# trill-breakout.net
KiCad netlist of a schematic drawn in EAGLE
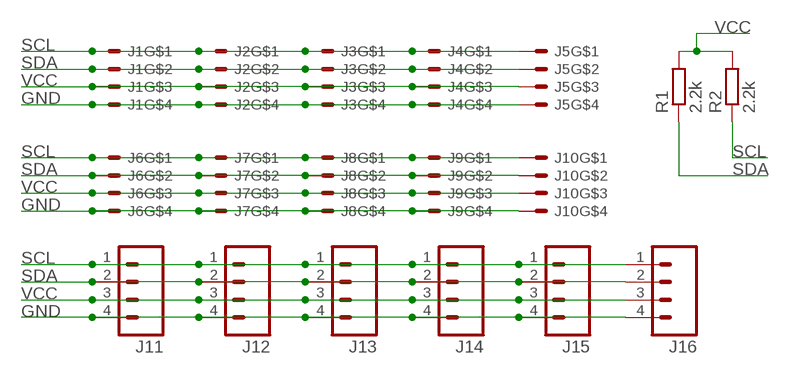
[diagram p0: schematic, sheet 1]

(export (version "E")
  (design (tool "Eeschema 10.0.6"))
  (components
    (comp (ref "J1")
      (value "GROVE-SMT")
      (footprint "eagle-import:JST-PH-4-SMT")
      (libsource (lib "eagle-import") (part "GROVE-SMT"))
    )
    (comp (ref "J2")
      (value "GROVE-SMT")
      (footprint "eagle-import:JST-PH-4-SMT")
      (libsource (lib "eagle-import") (part "GROVE-SMT"))
    )
    (comp (ref "J3")
      (value "GROVE-SMT")
      (footprint "eagle-import:JST-PH-4-SMT")
      (libsource (lib "eagle-import") (part "GROVE-SMT"))
    )
    (comp (ref "J4")
      (value "GROVE-SMT")
      (footprint "eagle-import:JST-PH-4-SMT")
      (libsource (lib "eagle-import") (part "GROVE-SMT"))
    )
    (comp (ref "J5")
      (value "GROVE-SMT")
      (footprint "eagle-import:JST-PH-4-SMT")
      (libsource (lib "eagle-import") (part "GROVE-SMT"))
    )
    (comp (ref "J6")
      (value "GROVE-SMT")
      (footprint "eagle-import:JST-PH-4-SMT")
      (libsource (lib "eagle-import") (part "GROVE-SMT"))
    )
    (comp (ref "J7")
      (value "GROVE-SMT")
      (footprint "eagle-import:JST-PH-4-SMT")
      (libsource (lib "eagle-import") (part "GROVE-SMT"))
    )
    (comp (ref "J8")
      (value "GROVE-SMT")
      (footprint "eagle-import:JST-PH-4-SMT")
      (libsource (lib "eagle-import") (part "GROVE-SMT"))
    )
    (comp (ref "J9")
      (value "GROVE-SMT")
      (footprint "eagle-import:JST-PH-4-SMT")
      (libsource (lib "eagle-import") (part "GROVE-SMT"))
    )
    (comp (ref "J10")
      (value "GROVE-SMT")
      (footprint "eagle-import:JST-PH-4-SMT")
      (libsource (lib "eagle-import") (part "GROVE-SMT"))
    )
    (comp (ref "J11")
      (value "M04LONGPADS")
      (footprint "eagle-import:1X04_LONGPADS")
      (libsource (lib "eagle-import") (part "M04LONGPADS"))
    )
    (comp (ref "J12")
      (value "M04LONGPADS")
      (footprint "eagle-import:1X04_LONGPADS")
      (libsource (lib "eagle-import") (part "M04LONGPADS"))
    )
    (comp (ref "J13")
      (value "M04LONGPADS")
      (footprint "eagle-import:1X04_LONGPADS")
      (libsource (lib "eagle-import") (part "M04LONGPADS"))
    )
    (comp (ref "J14")
      (value "M04LONGPADS")
      (footprint "eagle-import:1X04_LONGPADS")
      (libsource (lib "eagle-import") (part "M04LONGPADS"))
    )
    (comp (ref "J15")
      (value "M04LONGPADS")
      (footprint "eagle-import:1X04_LONGPADS")
      (libsource (lib "eagle-import") (part "M04LONGPADS"))
    )
    (comp (ref "J16")
      (value "M04LONGPADS")
      (footprint "eagle-import:1X04_LONGPADS")
      (libsource (lib "eagle-import") (part "M04LONGPADS"))
    )
    (comp (ref "R1")
      (value "2.2k")
      (footprint "eagle-import:R0603")
      (libsource (lib "eagle-import") (part "R-EU_R0603"))
    )
    (comp (ref "R2")
      (value "2.2k")
      (footprint "eagle-import:R0603")
      (libsource (lib "eagle-import") (part "R-EU_R0603"))
    )
  )
  (nets
    (net (code "1") (name "/GND") (class "Default")
      (node (ref "J1") (pin "4") (pinfunction "S_4") (pintype "passive"))
      (node (ref "J10") (pin "4") (pinfunction "S_4") (pintype "passive"))
      (node (ref "J11") (pin "4") (pinfunction "4_4") (pintype "passive"))
      (node (ref "J12") (pin "4") (pinfunction "4_4") (pintype "passive"))
      (node (ref "J13") (pin "4") (pinfunction "4_4") (pintype "passive"))
      (node (ref "J14") (pin "4") (pinfunction "4_4") (pintype "passive"))
      (node (ref "J15") (pin "4") (pinfunction "4_4") (pintype "passive"))
      (node (ref "J16") (pin "4") (pinfunction "4_4") (pintype "passive"))
      (node (ref "J2") (pin "4") (pinfunction "S_4") (pintype "passive"))
      (node (ref "J3") (pin "4") (pinfunction "S_4") (pintype "passive"))
      (node (ref "J4") (pin "4") (pinfunction "S_4") (pintype "passive"))
      (node (ref "J5") (pin "4") (pinfunction "S_4") (pintype "passive"))
      (node (ref "J6") (pin "4") (pinfunction "S_4") (pintype "passive"))
      (node (ref "J7") (pin "4") (pinfunction "S_4") (pintype "passive"))
      (node (ref "J8") (pin "4") (pinfunction "S_4") (pintype "passive"))
      (node (ref "J9") (pin "4") (pinfunction "S_4") (pintype "passive"))
    )
    (net (code "2") (name "/SCL") (class "Default")
      (node (ref "J1") (pin "1") (pinfunction "S_1") (pintype "passive"))
      (node (ref "J10") (pin "1") (pinfunction "S_1") (pintype "passive"))
      (node (ref "J11") (pin "1") (pinfunction "1_1") (pintype "passive"))
      (node (ref "J12") (pin "1") (pinfunction "1_1") (pintype "passive"))
      (node (ref "J13") (pin "1") (pinfunction "1_1") (pintype "passive"))
      (node (ref "J14") (pin "1") (pinfunction "1_1") (pintype "passive"))
      (node (ref "J15") (pin "1") (pinfunction "1_1") (pintype "passive"))
      (node (ref "J16") (pin "1") (pinfunction "1_1") (pintype "passive"))
      (node (ref "J2") (pin "1") (pinfunction "S_1") (pintype "passive"))
      (node (ref "J3") (pin "1") (pinfunction "S_1") (pintype "passive"))
      (node (ref "J4") (pin "1") (pinfunction "S_1") (pintype "passive"))
      (node (ref "J5") (pin "1") (pinfunction "S_1") (pintype "passive"))
      (node (ref "J6") (pin "1") (pinfunction "S_1") (pintype "passive"))
      (node (ref "J7") (pin "1") (pinfunction "S_1") (pintype "passive"))
      (node (ref "J8") (pin "1") (pinfunction "S_1") (pintype "passive"))
      (node (ref "J9") (pin "1") (pinfunction "S_1") (pintype "passive"))
      (node (ref "R2") (pin "1") (pinfunction "1_1") (pintype "passive"))
    )
    (net (code "3") (name "/SDA") (class "Default")
      (node (ref "J1") (pin "2") (pinfunction "S_2") (pintype "passive"))
      (node (ref "J10") (pin "2") (pinfunction "S_2") (pintype "passive"))
      (node (ref "J11") (pin "2") (pinfunction "2_2") (pintype "passive"))
      (node (ref "J12") (pin "2") (pinfunction "2_2") (pintype "passive"))
      (node (ref "J13") (pin "2") (pinfunction "2_2") (pintype "passive"))
      (node (ref "J14") (pin "2") (pinfunction "2_2") (pintype "passive"))
      (node (ref "J15") (pin "2") (pinfunction "2_2") (pintype "passive"))
      (node (ref "J16") (pin "2") (pinfunction "2_2") (pintype "passive"))
      (node (ref "J2") (pin "2") (pinfunction "S_2") (pintype "passive"))
      (node (ref "J3") (pin "2") (pinfunction "S_2") (pintype "passive"))
      (node (ref "J4") (pin "2") (pinfunction "S_2") (pintype "passive"))
      (node (ref "J5") (pin "2") (pinfunction "S_2") (pintype "passive"))
      (node (ref "J6") (pin "2") (pinfunction "S_2") (pintype "passive"))
      (node (ref "J7") (pin "2") (pinfunction "S_2") (pintype "passive"))
      (node (ref "J8") (pin "2") (pinfunction "S_2") (pintype "passive"))
      (node (ref "J9") (pin "2") (pinfunction "S_2") (pintype "passive"))
      (node (ref "R1") (pin "1") (pinfunction "1_1") (pintype "passive"))
    )
    (net (code "4") (name "/VCC") (class "Default")
      (node (ref "J1") (pin "3") (pinfunction "S_3") (pintype "passive"))
      (node (ref "J10") (pin "3") (pinfunction "S_3") (pintype "passive"))
      (node (ref "J11") (pin "3") (pinfunction "3_3") (pintype "passive"))
      (node (ref "J12") (pin "3") (pinfunction "3_3") (pintype "passive"))
      (node (ref "J13") (pin "3") (pinfunction "3_3") (pintype "passive"))
      (node (ref "J14") (pin "3") (pinfunction "3_3") (pintype "passive"))
      (node (ref "J15") (pin "3") (pinfunction "3_3") (pintype "passive"))
      (node (ref "J16") (pin "3") (pinfunction "3_3") (pintype "passive"))
      (node (ref "J2") (pin "3") (pinfunction "S_3") (pintype "passive"))
      (node (ref "J3") (pin "3") (pinfunction "S_3") (pintype "passive"))
      (node (ref "J4") (pin "3") (pinfunction "S_3") (pintype "passive"))
      (node (ref "J5") (pin "3") (pinfunction "S_3") (pintype "passive"))
      (node (ref "J6") (pin "3") (pinfunction "S_3") (pintype "passive"))
      (node (ref "J7") (pin "3") (pinfunction "S_3") (pintype "passive"))
      (node (ref "J8") (pin "3") (pinfunction "S_3") (pintype "passive"))
      (node (ref "J9") (pin "3") (pinfunction "S_3") (pintype "passive"))
      (node (ref "R1") (pin "2") (pinfunction "2_2") (pintype "passive"))
      (node (ref "R2") (pin "2") (pinfunction "2_2") (pintype "passive"))
    )
  )
)
